# SCH_ESP32_Panasonic_Aquarea_2023-09-12.net
KiCad netlist of a schematic drawn in EasyEDA
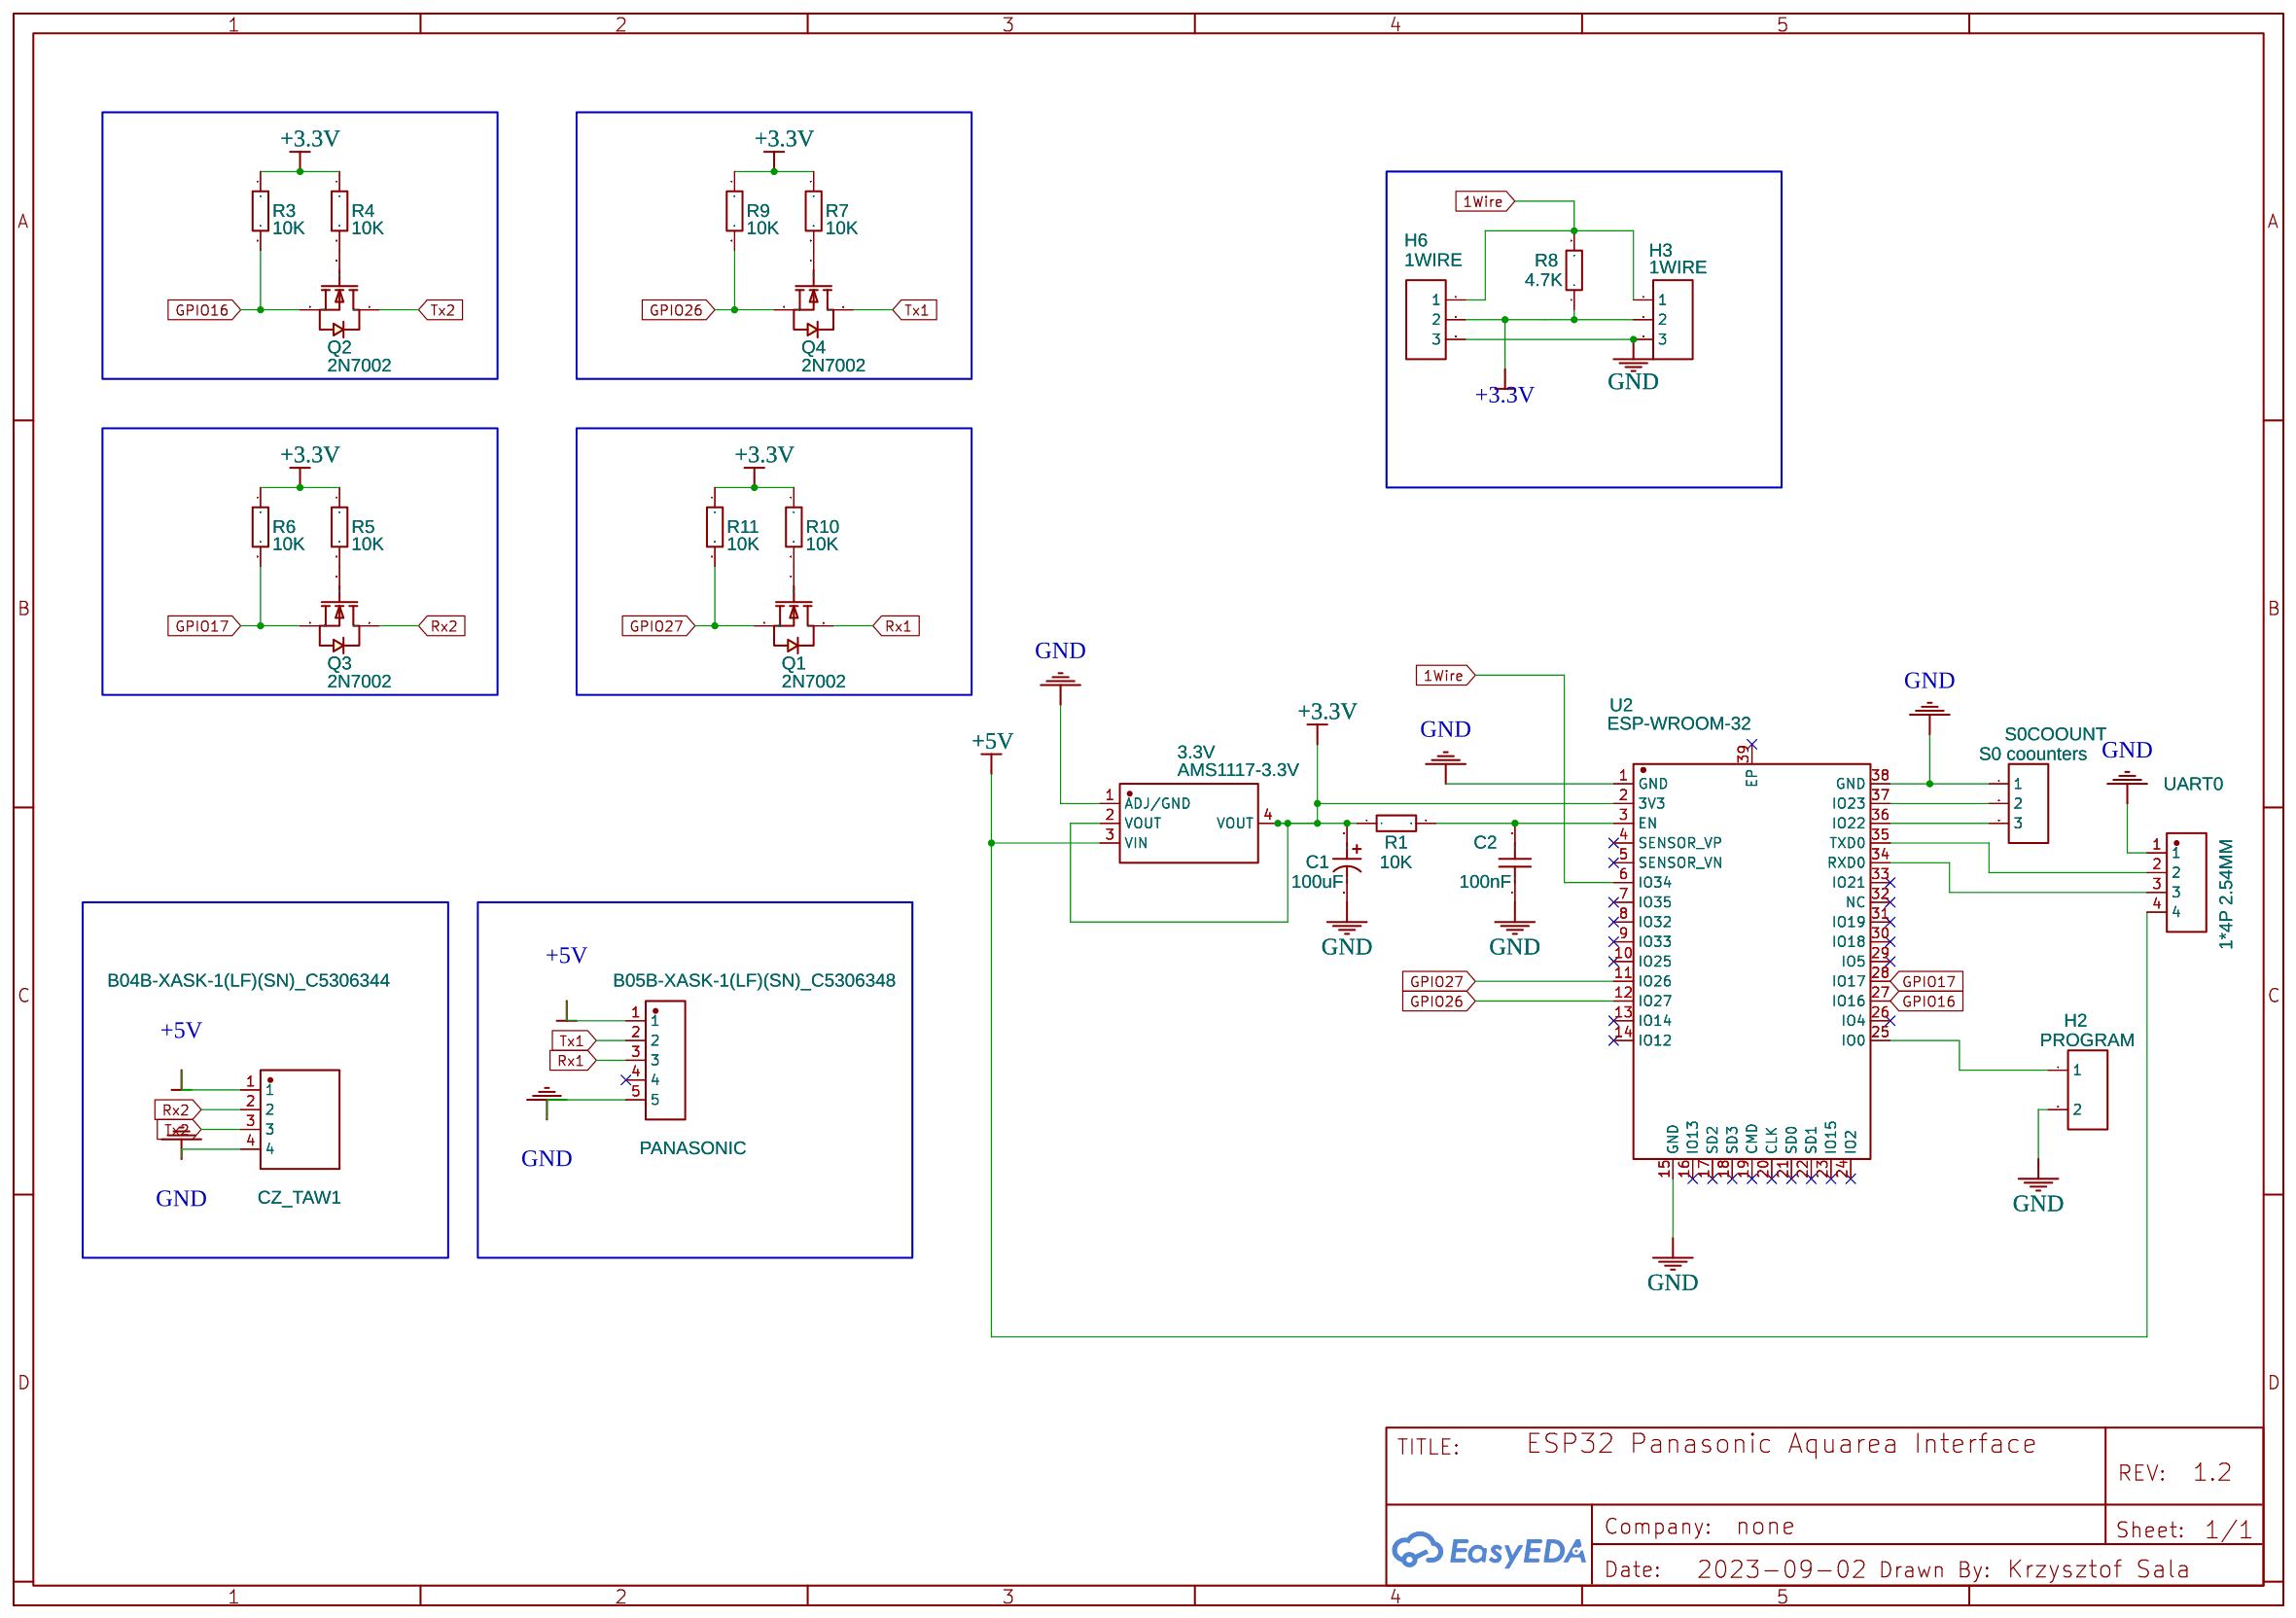
[diagram p0: schematic sheet]

(export (version "E")
  (design (tool "Eeschema 10.0.6"))
  (components
    (comp (ref "3.3V")
      (value "AMS1117-3.3V")
      (fields (field (name "Manufacturer") "WPMtek(维攀微)"))
      (libsource (lib "") (part "AMS1117-3.3V"))
    )
    (comp (ref "C1")
      (value "100uF")
      (fields (field (name "Manufacturer Part") "HS1C107M0507PC") (field (name "Manufacturer") "HONOR(荣誉)"))
      (libsource (lib "") (part "HS1C107M0507PC"))
    )
    (comp (ref "C2")
      (value "100nF")
      (fields
        (field (name "Manufacturer Part") "GRM31C5C1E104JA01L")
        (field (name "Manufacturer") "muRata(村田)")
      )
      (libsource (lib "") (part "GRM31C5C1E104JA01L_C426117"))
    )
    (comp (ref "CZ_TAW1")
      (value "B04B-XASK-1(LF)(SN)_C5306344")
      (fields (field (name "Manufacturer Part") "B04B-XASK-1(LF)(SN)") (field (name "Manufacturer") "JST"))
      (libsource (lib "") (part "B04B-XASK-1(LF)(SN)_C5306344"))
    )
    (comp (ref "H2")
      (value "PROGRAM")
      (fields (field (name "Manufacturer Part") "826629-2") (field (name "Manufacturer") "TE Connectivity"))
      (libsource (lib "") (part "Unknown_1045_545"))
    )
    (comp (ref "H3")
      (value "1WIRE")
      (fields (field (name "Manufacturer Part") "Header2.54mm 1*3P") (field (name "Manufacturer") "BOOMELE"))
      (libsource (lib "") (part "Unknown_835_155"))
    )
    (comp (ref "H6")
      (value "1WIRE")
      (fields (field (name "Manufacturer Part") "Header2.54mm 1*3P") (field (name "Manufacturer") "BOOMELE"))
      (libsource (lib "") (part "Unknown_720_155"))
    )
    (comp (ref "PANASONIC")
      (value "B05B-XASK-1(LF)(SN)_C5306348")
      (fields (field (name "Manufacturer Part") "B05B-XASK-1(LF)(SN)") (field (name "Manufacturer") "JST"))
      (libsource (lib "") (part "B05B-XASK-1(LF)(SN)_C5306348"))
    )
    (comp (ref "Q1")
      (value "2N7002")
      (fields (field (name "Manufacturer") "CJ"))
      (libsource (lib "") (part "Unknown_395_300"))
    )
    (comp (ref "Q2")
      (value "2N7002")
      (fields (field (name "Manufacturer") "CJ"))
      (libsource (lib "") (part "Unknown_165_140"))
    )
    (comp (ref "Q3")
      (value "2N7002")
      (fields (field (name "Manufacturer") "CJ"))
      (libsource (lib "") (part "Unknown_165_300"))
    )
    (comp (ref "Q4")
      (value "2N7002")
      (fields (field (name "Manufacturer") "CJ"))
      (libsource (lib "") (part "Unknown_405_140"))
    )
    (comp (ref "R1")
      (value "10K")
      (fields (field (name "Manufacturer Part") "0603WAF1002T5E") (field (name "Manufacturer") "UniOhm"))
      (libsource (lib "") (part "0603WAF1002T5E"))
    )
    (comp (ref "R3")
      (value "10K")
      (fields (field (name "Manufacturer Part") "0603WAF1002T5E") (field (name "Manufacturer") "UniOhm"))
      (libsource (lib "") (part "0603WAF1002T5E_1"))
    )
    (comp (ref "R4")
      (value "10K")
      (fields (field (name "Manufacturer Part") "0603WAF1002T5E") (field (name "Manufacturer") "UniOhm"))
      (libsource (lib "") (part "0603WAF1002T5E_1"))
    )
    (comp (ref "R5")
      (value "10K")
      (fields (field (name "Manufacturer Part") "0603WAF1002T5E") (field (name "Manufacturer") "UniOhm"))
      (libsource (lib "") (part "0603WAF1002T5E_1"))
    )
    (comp (ref "R6")
      (value "10K")
      (fields (field (name "Manufacturer Part") "0603WAF1002T5E") (field (name "Manufacturer") "UniOhm"))
      (libsource (lib "") (part "0603WAF1002T5E_1"))
    )
    (comp (ref "R7")
      (value "10K")
      (fields (field (name "Manufacturer Part") "0603WAF1002T5E") (field (name "Manufacturer") "UniOhm"))
      (libsource (lib "") (part "0603WAF1002T5E_1"))
    )
    (comp (ref "R8")
      (value "4.7K")
      (fields (field (name "Manufacturer Part") "0603WAF4701T5E") (field (name "Manufacturer") "UniOhm"))
      (libsource (lib "") (part "0603WAF4701T5E"))
    )
    (comp (ref "R9")
      (value "10K")
      (fields (field (name "Manufacturer Part") "0603WAF1002T5E") (field (name "Manufacturer") "UniOhm"))
      (libsource (lib "") (part "0603WAF1002T5E_1"))
    )
    (comp (ref "R10")
      (value "10K")
      (fields (field (name "Manufacturer Part") "0603WAF1002T5E") (field (name "Manufacturer") "UniOhm"))
      (libsource (lib "") (part "0603WAF1002T5E_1"))
    )
    (comp (ref "R11")
      (value "10K")
      (fields (field (name "Manufacturer Part") "0603WAF1002T5E") (field (name "Manufacturer") "UniOhm"))
      (libsource (lib "") (part "0603WAF1002T5E_1"))
    )
    (comp (ref "S0COOUNT")
      (value "S0 coounters")
      (fields (field (name "Manufacturer Part") "Header2.54mm 1*3P") (field (name "Manufacturer") "BOOMELE"))
      (libsource (lib "") (part "Unknown_1015_400"))
    )
    (comp (ref "U2")
      (value "ESP-WROOM-32")
      (fields
        (field (name "Manufacturer Part") "ESP32-WROOM-32")
        (field (name "Manufacturer") "ESPRESSIF(乐鑫)")
      )
      (libsource (lib "") (part "ESP-WROOM-32"))
    )
    (comp (ref "UART0")
      (value "1*4P 2.54MM")
      (fields (field (name "Manufacturer Part") "单排直插排针 1*4P 2.54mm"))
      (libsource (lib "") (part "1*4P 2.54MM"))
    )
  )
  (nets
    (net (code "1") (name "+3.3V") (class "Default")
      (node (ref "3.3V") (pin "2") (pinfunction "VOUT_2") (pintype "unspecified"))
      (node (ref "3.3V") (pin "4") (pinfunction "VOUT_4") (pintype "unspecified"))
      (node (ref "C1") (pin "1") (pinfunction "1_1") (pintype "input"))
      (node (ref "H3") (pin "2") (pinfunction "2_2") (pintype "input"))
      (node (ref "H6") (pin "2") (pinfunction "2_2") (pintype "input"))
      (node (ref "R1") (pin "1") (pinfunction "1_1") (pintype "input"))
      (node (ref "R10") (pin "1") (pinfunction "1_1") (pintype "input"))
      (node (ref "R11") (pin "1") (pinfunction "1_1") (pintype "input"))
      (node (ref "R3") (pin "1") (pinfunction "1_1") (pintype "input"))
      (node (ref "R4") (pin "1") (pinfunction "1_1") (pintype "input"))
      (node (ref "R5") (pin "1") (pinfunction "1_1") (pintype "input"))
      (node (ref "R6") (pin "1") (pinfunction "1_1") (pintype "input"))
      (node (ref "R7") (pin "1") (pinfunction "1_1") (pintype "input"))
      (node (ref "R8") (pin "1") (pinfunction "1_1") (pintype "input"))
      (node (ref "R9") (pin "1") (pinfunction "1_1") (pintype "input"))
      (node (ref "U2") (pin "2") (pinfunction "3V3_2") (pintype "unspecified"))
    )
    (net (code "2") (name "+5V") (class "Default")
      (node (ref "3.3V") (pin "3") (pinfunction "VIN_3") (pintype "unspecified"))
      (node (ref "CZ_TAW1") (pin "1") (pinfunction "1_1") (pintype "unspecified"))
      (node (ref "PANASONIC") (pin "1") (pinfunction "1_1") (pintype "unspecified"))
      (node (ref "UART0") (pin "4") (pinfunction "4_4") (pintype "unspecified"))
    )
    (net (code "3") (name "1Wire") (class "Default")
      (node (ref "H3") (pin "1") (pinfunction "1_1") (pintype "input"))
      (node (ref "H6") (pin "1") (pinfunction "1_1") (pintype "input"))
      (node (ref "R8") (pin "2") (pinfunction "2_2") (pintype "input"))
      (node (ref "U2") (pin "6") (pinfunction "IO34_6") (pintype "unspecified"))
    )
    (net (code "4") (name "GND") (class "Default")
      (node (ref "3.3V") (pin "1") (pinfunction "ADJ/GND_1") (pintype "unspecified"))
      (node (ref "C1") (pin "2") (pinfunction "2_2") (pintype "input"))
      (node (ref "C2") (pin "1") (pinfunction "1_1") (pintype "unspecified"))
      (node (ref "CZ_TAW1") (pin "4") (pinfunction "4_4") (pintype "unspecified"))
      (node (ref "H2") (pin "2") (pinfunction "2_2") (pintype "unspecified"))
      (node (ref "H3") (pin "3") (pinfunction "3_3") (pintype "input"))
      (node (ref "H6") (pin "3") (pinfunction "3_3") (pintype "input"))
      (node (ref "PANASONIC") (pin "5") (pinfunction "5_5") (pintype "unspecified"))
      (node (ref "S0COOUNT") (pin "1") (pinfunction "1_1") (pintype "input"))
      (node (ref "U2") (pin "1") (pinfunction "GND_1") (pintype "unspecified"))
      (node (ref "U2") (pin "15") (pinfunction "GND_15") (pintype "unspecified"))
      (node (ref "U2") (pin "38") (pinfunction "GND_38") (pintype "unspecified"))
      (node (ref "UART0") (pin "1") (pinfunction "1_1") (pintype "unspecified"))
    )
    (net (code "5") (name "GPIO16") (class "Default")
      (node (ref "Q2") (pin "2") (pinfunction "S_2") (pintype "unspecified"))
      (node (ref "R3") (pin "2") (pinfunction "2_2") (pintype "input"))
      (node (ref "U2") (pin "27") (pinfunction "IO16_27") (pintype "unspecified"))
    )
    (net (code "6") (name "GPIO17") (class "Default")
      (node (ref "Q3") (pin "2") (pinfunction "S_2") (pintype "unspecified"))
      (node (ref "R6") (pin "2") (pinfunction "2_2") (pintype "input"))
      (node (ref "U2") (pin "28") (pinfunction "IO17_28") (pintype "unspecified"))
    )
    (net (code "7") (name "GPIO26") (class "Default")
      (node (ref "Q4") (pin "2") (pinfunction "S_2") (pintype "unspecified"))
      (node (ref "R9") (pin "2") (pinfunction "2_2") (pintype "input"))
      (node (ref "U2") (pin "12") (pinfunction "IO27_12") (pintype "unspecified"))
    )
    (net (code "8") (name "GPIO27") (class "Default")
      (node (ref "Q1") (pin "2") (pinfunction "S_2") (pintype "unspecified"))
      (node (ref "R11") (pin "2") (pinfunction "2_2") (pintype "input"))
      (node (ref "U2") (pin "11") (pinfunction "IO26_11") (pintype "unspecified"))
    )
    (net (code "9") (name "Net-(Q1-G)") (class "Default")
      (node (ref "Q1") (pin "1") (pinfunction "G_1") (pintype "unspecified"))
      (node (ref "R10") (pin "2") (pinfunction "2_2") (pintype "input"))
    )
    (net (code "10") (name "Net-(Q2-G)") (class "Default")
      (node (ref "Q2") (pin "1") (pinfunction "G_1") (pintype "unspecified"))
      (node (ref "R4") (pin "2") (pinfunction "2_2") (pintype "input"))
    )
    (net (code "11") (name "Net-(Q3-G)") (class "Default")
      (node (ref "Q3") (pin "1") (pinfunction "G_1") (pintype "unspecified"))
      (node (ref "R5") (pin "2") (pinfunction "2_2") (pintype "input"))
    )
    (net (code "12") (name "Net-(Q4-G)") (class "Default")
      (node (ref "Q4") (pin "1") (pinfunction "G_1") (pintype "unspecified"))
      (node (ref "R7") (pin "2") (pinfunction "2_2") (pintype "input"))
    )
    (net (code "13") (name "Net-(U2-EN)") (class "Default")
      (node (ref "C2") (pin "2") (pinfunction "2_2") (pintype "unspecified"))
      (node (ref "R1") (pin "2") (pinfunction "2_2") (pintype "input"))
      (node (ref "U2") (pin "3") (pinfunction "EN_3") (pintype "unspecified"))
    )
    (net (code "14") (name "Net-(U2-IO0)") (class "Default")
      (node (ref "H2") (pin "1") (pinfunction "1_1") (pintype "unspecified"))
      (node (ref "U2") (pin "25") (pinfunction "IO0_25") (pintype "unspecified"))
    )
    (net (code "15") (name "Net-(U2-IO22)") (class "Default")
      (node (ref "S0COOUNT") (pin "3") (pinfunction "3_3") (pintype "input"))
      (node (ref "U2") (pin "36") (pinfunction "IO22_36") (pintype "unspecified"))
    )
    (net (code "16") (name "Net-(U2-IO23)") (class "Default")
      (node (ref "S0COOUNT") (pin "2") (pinfunction "2_2") (pintype "input"))
      (node (ref "U2") (pin "37") (pinfunction "IO23_37") (pintype "unspecified"))
    )
    (net (code "17") (name "Net-(U2-RXD0)") (class "Default")
      (node (ref "U2") (pin "34") (pinfunction "RXD0_34") (pintype "unspecified"))
      (node (ref "UART0") (pin "3") (pinfunction "3_3") (pintype "unspecified"))
    )
    (net (code "18") (name "Net-(U2-TXD0)") (class "Default")
      (node (ref "U2") (pin "35") (pinfunction "TXD0_35") (pintype "unspecified"))
      (node (ref "UART0") (pin "2") (pinfunction "2_2") (pintype "unspecified"))
    )
    (net (code "19") (name "Rx1") (class "Default")
      (node (ref "PANASONIC") (pin "3") (pinfunction "3_3") (pintype "unspecified"))
      (node (ref "Q1") (pin "3") (pinfunction "D_3") (pintype "unspecified"))
    )
    (net (code "20") (name "Rx2") (class "Default")
      (node (ref "CZ_TAW1") (pin "2") (pinfunction "2_2") (pintype "unspecified"))
      (node (ref "Q3") (pin "3") (pinfunction "D_3") (pintype "unspecified"))
    )
    (net (code "21") (name "Tx1") (class "Default")
      (node (ref "PANASONIC") (pin "2") (pinfunction "2_2") (pintype "unspecified"))
      (node (ref "Q4") (pin "3") (pinfunction "D_3") (pintype "unspecified"))
    )
    (net (code "22") (name "Tx2") (class "Default")
      (node (ref "CZ_TAW1") (pin "3") (pinfunction "3_3") (pintype "unspecified"))
      (node (ref "Q2") (pin "3") (pinfunction "D_3") (pintype "unspecified"))
    )
    (net (code "23") (name "unconnected-(PANASONIC-Pad4)") (class "Default")
      (node (ref "PANASONIC") (pin "4") (pinfunction "4_4") (pintype "unspecified+no_connect"))
    )
    (net (code "24") (name "unconnected-(U2-CLK-Pad20)") (class "Default")
      (node (ref "U2") (pin "20") (pinfunction "CLK_20") (pintype "unspecified+no_connect"))
    )
    (net (code "25") (name "unconnected-(U2-CMD-Pad19)") (class "Default")
      (node (ref "U2") (pin "19") (pinfunction "CMD_19") (pintype "unspecified+no_connect"))
    )
    (net (code "26") (name "unconnected-(U2-EP-Pad39)") (class "Default")
      (node (ref "U2") (pin "39") (pinfunction "EP_39") (pintype "unspecified+no_connect"))
    )
    (net (code "27") (name "unconnected-(U2-IO2-Pad24)") (class "Default")
      (node (ref "U2") (pin "24") (pinfunction "IO2_24") (pintype "unspecified+no_connect"))
    )
    (net (code "28") (name "unconnected-(U2-IO4-Pad26)") (class "Default")
      (node (ref "U2") (pin "26") (pinfunction "IO4_26") (pintype "unspecified+no_connect"))
    )
    (net (code "29") (name "unconnected-(U2-IO5-Pad29)") (class "Default")
      (node (ref "U2") (pin "29") (pinfunction "IO5_29") (pintype "unspecified+no_connect"))
    )
    (net (code "30") (name "unconnected-(U2-IO12-Pad14)") (class "Default")
      (node (ref "U2") (pin "14") (pinfunction "IO12_14") (pintype "unspecified+no_connect"))
    )
    (net (code "31") (name "unconnected-(U2-IO13-Pad16)") (class "Default")
      (node (ref "U2") (pin "16") (pinfunction "IO13_16") (pintype "unspecified+no_connect"))
    )
    (net (code "32") (name "unconnected-(U2-IO14-Pad13)") (class "Default")
      (node (ref "U2") (pin "13") (pinfunction "IO14_13") (pintype "unspecified+no_connect"))
    )
    (net (code "33") (name "unconnected-(U2-IO15-Pad23)") (class "Default")
      (node (ref "U2") (pin "23") (pinfunction "IO15_23") (pintype "unspecified+no_connect"))
    )
    (net (code "34") (name "unconnected-(U2-IO18-Pad30)") (class "Default")
      (node (ref "U2") (pin "30") (pinfunction "IO18_30") (pintype "unspecified+no_connect"))
    )
    (net (code "35") (name "unconnected-(U2-IO19-Pad31)") (class "Default")
      (node (ref "U2") (pin "31") (pinfunction "IO19_31") (pintype "unspecified+no_connect"))
    )
    (net (code "36") (name "unconnected-(U2-IO21-Pad33)") (class "Default")
      (node (ref "U2") (pin "33") (pinfunction "IO21_33") (pintype "unspecified+no_connect"))
    )
    (net (code "37") (name "unconnected-(U2-IO25-Pad10)") (class "Default")
      (node (ref "U2") (pin "10") (pinfunction "IO25_10") (pintype "unspecified+no_connect"))
    )
    (net (code "38") (name "unconnected-(U2-IO32-Pad8)") (class "Default")
      (node (ref "U2") (pin "8") (pinfunction "IO32_8") (pintype "unspecified+no_connect"))
    )
    (net (code "39") (name "unconnected-(U2-IO33-Pad9)") (class "Default")
      (node (ref "U2") (pin "9") (pinfunction "IO33_9") (pintype "unspecified+no_connect"))
    )
    (net (code "40") (name "unconnected-(U2-IO35-Pad7)") (class "Default")
      (node (ref "U2") (pin "7") (pinfunction "IO35_7") (pintype "unspecified+no_connect"))
    )
    (net (code "41") (name "unconnected-(U2-NC-Pad32)") (class "Default")
      (node (ref "U2") (pin "32") (pinfunction "NC_32") (pintype "unspecified+no_connect"))
    )
    (net (code "42") (name "unconnected-(U2-SD0-Pad21)") (class "Default")
      (node (ref "U2") (pin "21") (pinfunction "SD0_21") (pintype "unspecified+no_connect"))
    )
    (net (code "43") (name "unconnected-(U2-SD1-Pad22)") (class "Default")
      (node (ref "U2") (pin "22") (pinfunction "SD1_22") (pintype "unspecified+no_connect"))
    )
    (net (code "44") (name "unconnected-(U2-SD2-Pad17)") (class "Default")
      (node (ref "U2") (pin "17") (pinfunction "SD2_17") (pintype "unspecified+no_connect"))
    )
    (net (code "45") (name "unconnected-(U2-SD3-Pad18)") (class "Default")
      (node (ref "U2") (pin "18") (pinfunction "SD3_18") (pintype "unspecified+no_connect"))
    )
    (net (code "46") (name "unconnected-(U2-SENSOR_VN-Pad5)") (class "Default")
      (node (ref "U2") (pin "5") (pinfunction "SENSOR_VN_5") (pintype "unspecified+no_connect"))
    )
    (net (code "47") (name "unconnected-(U2-SENSOR_VP-Pad4)") (class "Default")
      (node (ref "U2") (pin "4") (pinfunction "SENSOR_VP_4") (pintype "unspecified+no_connect"))
    )
  )
)
